# ADC.net
KiCad netlist of a schematic drawn in Altium Designer
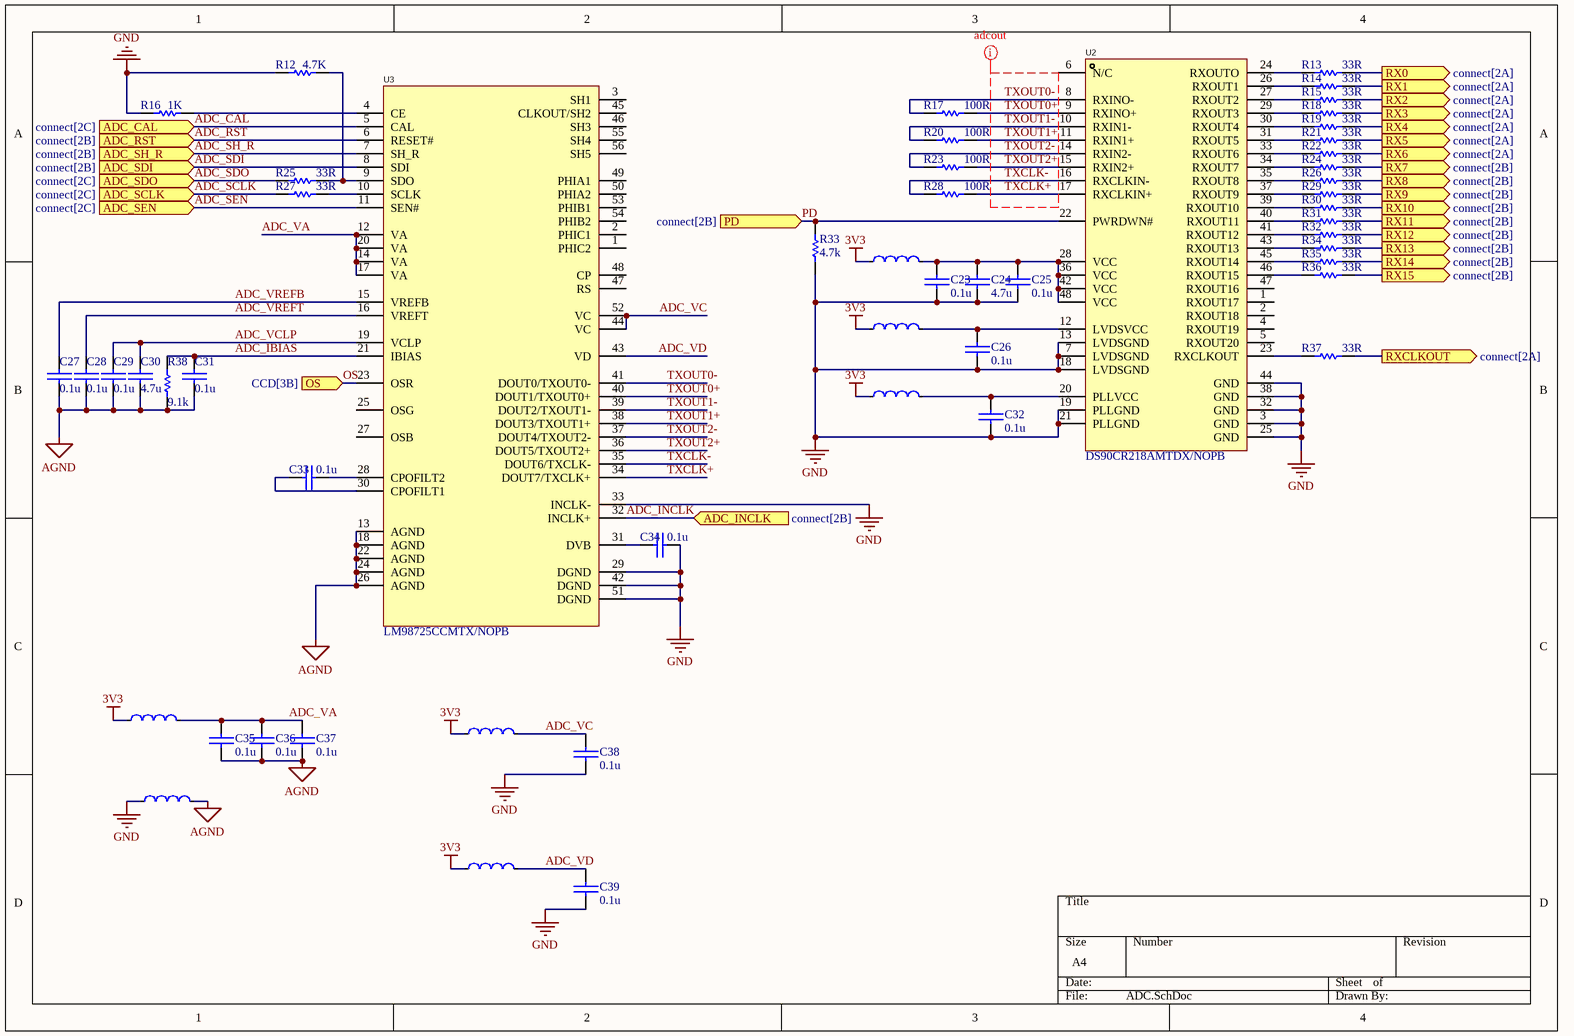
[diagram p0: ADC.SchDoc]

(export (version "E")
  (design (tool "Eeschema 10.0.6"))
  (components
    (comp (ref "C23")
      (value "0.1u")
      (footprint "0603C")
      (description "无极性电容")
      (libsource (lib "1.00-阻容感") (part "CAP"))
    )
    (comp (ref "C24")
      (value "4.7u")
      (footprint "0603C")
      (description "无极性电容")
      (libsource (lib "1.00-阻容感") (part "CAP"))
    )
    (comp (ref "C25")
      (value "0.1u")
      (footprint "0603C")
      (description "无极性电容")
      (libsource (lib "1.00-阻容感") (part "CAP"))
    )
    (comp (ref "C26")
      (value "0.1u")
      (footprint "0603C")
      (description "无极性电容")
      (libsource (lib "1.00-阻容感") (part "CAP"))
    )
    (comp (ref "C27")
      (value "0.1u")
      (footprint "0603C")
      (description "无极性电容")
      (libsource (lib "1.00-阻容感") (part "CAP"))
    )
    (comp (ref "C28")
      (value "0.1u")
      (footprint "0603C")
      (description "无极性电容")
      (libsource (lib "1.00-阻容感") (part "CAP"))
    )
    (comp (ref "C29")
      (value "0.1u")
      (footprint "0603C")
      (description "无极性电容")
      (libsource (lib "1.00-阻容感") (part "CAP"))
    )
    (comp (ref "C30")
      (value "4.7u")
      (footprint "0603C")
      (description "无极性电容")
      (libsource (lib "1.00-阻容感") (part "CAP"))
    )
    (comp (ref "C31")
      (value "0.1u")
      (footprint "0603C")
      (description "无极性电容")
      (libsource (lib "1.00-阻容感") (part "CAP"))
    )
    (comp (ref "C32")
      (value "0.1u")
      (footprint "0603C")
      (description "无极性电容")
      (libsource (lib "1.00-阻容感") (part "CAP"))
    )
    (comp (ref "C33")
      (value "0.1u")
      (footprint "0603C")
      (description "无极性电容")
      (libsource (lib "1.00-阻容感") (part "CAP"))
    )
    (comp (ref "C34")
      (value "0.1u")
      (footprint "0603C")
      (description "无极性电容")
      (libsource (lib "1.00-阻容感") (part "CAP"))
    )
    (comp (ref "C35")
      (value "0.1u")
      (footprint "0603C")
      (description "无极性电容")
      (libsource (lib "1.00-阻容感") (part "CAP"))
    )
    (comp (ref "C36")
      (value "0.1u")
      (footprint "0603C")
      (description "无极性电容")
      (libsource (lib "1.00-阻容感") (part "CAP"))
    )
    (comp (ref "C37")
      (value "0.1u")
      (footprint "0603C")
      (description "无极性电容")
      (libsource (lib "1.00-阻容感") (part "CAP"))
    )
    (comp (ref "C38")
      (value "0.1u")
      (footprint "0603C")
      (description "无极性电容")
      (libsource (lib "1.00-阻容感") (part "CAP"))
    )
    (comp (ref "C39")
      (value "0.1u")
      (footprint "0603C")
      (description "无极性电容")
      (libsource (lib "1.00-阻容感") (part "CAP"))
    )
    (comp (ref "L4")
      (value "GZ1608D601TF")
      (footprint "0603L")
      (description "铁氧体磁珠")
      (fields (field (name "MANUFACTURER") "Sunlord(顺络)") (field (name "TOLERANCE") "±25%"))
      (libsource (lib "1.00-阻容感") (part "FB"))
    )
    (comp (ref "L5")
      (value "GZ1608D601TF")
      (footprint "0603L")
      (description "铁氧体磁珠")
      (fields (field (name "MANUFACTURER") "Sunlord(顺络)") (field (name "TOLERANCE") "±25%"))
      (libsource (lib "1.00-阻容感") (part "FB"))
    )
    (comp (ref "L6")
      (value "GZ1608D601TF")
      (footprint "0603L")
      (description "铁氧体磁珠")
      (fields (field (name "MANUFACTURER") "Sunlord(顺络)") (field (name "TOLERANCE") "±25%"))
      (libsource (lib "1.00-阻容感") (part "FB"))
    )
    (comp (ref "L7")
      (value "GZ1608D601TF")
      (footprint "0603L")
      (description "铁氧体磁珠")
      (fields (field (name "MANUFACTURER") "Sunlord(顺络)") (field (name "TOLERANCE") "±25%"))
      (libsource (lib "1.00-阻容感") (part "FB"))
    )
    (comp (ref "L8")
      (value "GZ1608D601TF")
      (footprint "0603L")
      (description "铁氧体磁珠")
      (fields (field (name "MANUFACTURER") "Sunlord(顺络)") (field (name "TOLERANCE") "±25%"))
      (libsource (lib "1.00-阻容感") (part "FB"))
    )
    (comp (ref "L9")
      (value "GZ1608D601TF")
      (footprint "0603L")
      (description "铁氧体磁珠")
      (fields (field (name "MANUFACTURER") "Sunlord(顺络)") (field (name "TOLERANCE") "±25%"))
      (libsource (lib "1.00-阻容感") (part "FB"))
    )
    (comp (ref "L10")
      (value "GZ1608D601TF")
      (footprint "0603L")
      (description "铁氧体磁珠")
      (fields (field (name "MANUFACTURER") "Sunlord(顺络)") (field (name "TOLERANCE") "±25%"))
      (libsource (lib "1.00-阻容感") (part "FB"))
    )
    (comp (ref "R12")
      (value "4.7K")
      (footprint "0603R")
      (description "电阻")
      (libsource (lib "1.00-阻容感") (part "RES"))
    )
    (comp (ref "R13")
      (value "33R")
      (footprint "0603R")
      (description "电阻")
      (libsource (lib "1.00-阻容感") (part "RES"))
    )
    (comp (ref "R14")
      (value "33R")
      (footprint "0603R")
      (description "电阻")
      (libsource (lib "1.00-阻容感") (part "RES"))
    )
    (comp (ref "R15")
      (value "33R")
      (footprint "0603R")
      (description "电阻")
      (libsource (lib "1.00-阻容感") (part "RES"))
    )
    (comp (ref "R16")
      (value "1K")
      (footprint "0603R")
      (description "电阻")
      (libsource (lib "1.00-阻容感") (part "RES"))
    )
    (comp (ref "R17")
      (value "100R")
      (footprint "0603R")
      (description "电阻")
      (libsource (lib "1.00-阻容感") (part "RES"))
    )
    (comp (ref "R18")
      (value "33R")
      (footprint "0603R")
      (description "电阻")
      (libsource (lib "1.00-阻容感") (part "RES"))
    )
    (comp (ref "R19")
      (value "33R")
      (footprint "0603R")
      (description "电阻")
      (libsource (lib "1.00-阻容感") (part "RES"))
    )
    (comp (ref "R20")
      (value "100R")
      (footprint "0603R")
      (description "电阻")
      (libsource (lib "1.00-阻容感") (part "RES"))
    )
    (comp (ref "R21")
      (value "33R")
      (footprint "0603R")
      (description "电阻")
      (libsource (lib "1.00-阻容感") (part "RES"))
    )
    (comp (ref "R22")
      (value "33R")
      (footprint "0603R")
      (description "电阻")
      (libsource (lib "1.00-阻容感") (part "RES"))
    )
    (comp (ref "R23")
      (value "100R")
      (footprint "0603R")
      (description "电阻")
      (libsource (lib "1.00-阻容感") (part "RES"))
    )
    (comp (ref "R24")
      (value "33R")
      (footprint "0603R")
      (description "电阻")
      (libsource (lib "1.00-阻容感") (part "RES"))
    )
    (comp (ref "R25")
      (value "33R")
      (footprint "0603R")
      (description "电阻")
      (libsource (lib "1.00-阻容感") (part "RES"))
    )
    (comp (ref "R26")
      (value "33R")
      (footprint "0603R")
      (description "电阻")
      (libsource (lib "1.00-阻容感") (part "RES"))
    )
    (comp (ref "R27")
      (value "33R")
      (footprint "0603R")
      (description "电阻")
      (libsource (lib "1.00-阻容感") (part "RES"))
    )
    (comp (ref "R28")
      (value "100R")
      (footprint "0603R")
      (description "电阻")
      (libsource (lib "1.00-阻容感") (part "RES"))
    )
    (comp (ref "R29")
      (value "33R")
      (footprint "0603R")
      (description "电阻")
      (libsource (lib "1.00-阻容感") (part "RES"))
    )
    (comp (ref "R30")
      (value "33R")
      (footprint "0603R")
      (description "电阻")
      (libsource (lib "1.00-阻容感") (part "RES"))
    )
    (comp (ref "R31")
      (value "33R")
      (footprint "0603R")
      (description "电阻")
      (libsource (lib "1.00-阻容感") (part "RES"))
    )
    (comp (ref "R32")
      (value "33R")
      (footprint "0603R")
      (description "电阻")
      (libsource (lib "1.00-阻容感") (part "RES"))
    )
    (comp (ref "R33")
      (value "4.7k")
      (footprint "0603R")
      (description "电阻")
      (libsource (lib "1.00-阻容感") (part "RES"))
    )
    (comp (ref "R34")
      (value "33R")
      (footprint "0603R")
      (description "电阻")
      (libsource (lib "1.00-阻容感") (part "RES"))
    )
    (comp (ref "R35")
      (value "33R")
      (footprint "0603R")
      (description "电阻")
      (libsource (lib "1.00-阻容感") (part "RES"))
    )
    (comp (ref "R36")
      (value "33R")
      (footprint "0603R")
      (description "电阻")
      (libsource (lib "1.00-阻容感") (part "RES"))
    )
    (comp (ref "R37")
      (value "33R")
      (footprint "0603R")
      (description "电阻")
      (libsource (lib "1.00-阻容感") (part "RES"))
    )
    (comp (ref "R38")
      (value "9.1k")
      (footprint "0603R")
      (description "电阻")
      (libsource (lib "1.00-阻容感") (part "RES"))
    )
    (comp (ref "U2")
      (value "DS90CR218AMTDX/NOPB")
      (footprint "TSSOP-48")
      (description "解串芯片")
      (fields (field (name "MANUFACTURER") "TI(德州仪器)"))
      (libsource (lib "0.05-mylib") (part "DS90CR218AMTDX/NOPB"))
    )
    (comp (ref "U3")
      (value "LM98725CCMTX/NOPB")
      (footprint "TSSOP-56")
      (description "CCD专用ADC")
      (fields (field (name "MANUFACTURER") "TI(德州仪器)"))
      (libsource (lib "0.05-mylib") (part "LM98725CCMTX/NOPB"))
    )
  )
  (nets
    (net (code "1") (name "/ADC_CAL") (class "Default")
      (node (ref "U3") (pin "5") (pinfunction "CAL_5") (pintype "passive"))
    )
    (net (code "2") (name "/ADC_IBIAS") (class "Default")
      (node (ref "C31") (pin "1") (pinfunction "1_1") (pintype "passive"))
      (node (ref "R38") (pin "2") (pinfunction "2_2") (pintype "passive"))
      (node (ref "U3") (pin "21") (pinfunction "IBIAS_21") (pintype "passive"))
    )
    (net (code "3") (name "/ADC_INCLK") (class "Default")
      (node (ref "U3") (pin "32") (pinfunction "INCLK+_32") (pintype "passive"))
    )
    (net (code "4") (name "/ADC_RST") (class "Default")
      (node (ref "U3") (pin "6") (pinfunction "RESET#_6") (pintype "passive"))
    )
    (net (code "5") (name "/ADC_SCLK") (class "Default")
      (node (ref "R27") (pin "1") (pinfunction "1_1") (pintype "passive"))
    )
    (net (code "6") (name "/ADC_SDI") (class "Default")
      (node (ref "U3") (pin "8") (pinfunction "SDI_8") (pintype "passive"))
    )
    (net (code "7") (name "/ADC_SDO") (class "Default")
      (node (ref "R25") (pin "1") (pinfunction "1_1") (pintype "passive"))
    )
    (net (code "8") (name "/ADC_SEN") (class "Default")
      (node (ref "U3") (pin "11") (pinfunction "SEN#_11") (pintype "passive"))
    )
    (net (code "9") (name "/ADC_SH_R") (class "Default")
      (node (ref "U3") (pin "7") (pinfunction "SH_R_7") (pintype "passive"))
    )
    (net (code "10") (name "/ADC_VA") (class "Default")
      (node (ref "C35") (pin "2") (pinfunction "2_2") (pintype "passive"))
      (node (ref "C36") (pin "2") (pinfunction "2_2") (pintype "passive"))
      (node (ref "C37") (pin "2") (pinfunction "2_2") (pintype "passive"))
      (node (ref "L7") (pin "2") (pinfunction "2_2") (pintype "passive"))
      (node (ref "U3") (pin "12") (pinfunction "VA_12") (pintype "passive"))
      (node (ref "U3") (pin "14") (pinfunction "VA_14") (pintype "passive"))
      (node (ref "U3") (pin "17") (pinfunction "VA_17") (pintype "passive"))
      (node (ref "U3") (pin "20") (pinfunction "VA_20") (pintype "passive"))
    )
    (net (code "11") (name "/ADC_VC") (class "Default")
      (node (ref "C38") (pin "2") (pinfunction "2_2") (pintype "passive"))
      (node (ref "L8") (pin "2") (pinfunction "2_2") (pintype "passive"))
      (node (ref "U3") (pin "44") (pinfunction "VC_44") (pintype "passive"))
      (node (ref "U3") (pin "52") (pinfunction "VC_52") (pintype "passive"))
    )
    (net (code "12") (name "/ADC_VCLP") (class "Default")
      (node (ref "C29") (pin "1") (pinfunction "1_1") (pintype "passive"))
      (node (ref "C30") (pin "1") (pinfunction "1_1") (pintype "passive"))
      (node (ref "U3") (pin "19") (pinfunction "VCLP_19") (pintype "passive"))
    )
    (net (code "13") (name "/ADC_VD") (class "Default")
      (node (ref "C39") (pin "2") (pinfunction "2_2") (pintype "passive"))
      (node (ref "L10") (pin "2") (pinfunction "2_2") (pintype "passive"))
      (node (ref "U3") (pin "43") (pinfunction "VD_43") (pintype "passive"))
    )
    (net (code "14") (name "/ADC_VREFB") (class "Default")
      (node (ref "C27") (pin "1") (pinfunction "1_1") (pintype "passive"))
      (node (ref "U3") (pin "15") (pinfunction "VREFB_15") (pintype "passive"))
    )
    (net (code "15") (name "/ADC_VREFT") (class "Default")
      (node (ref "C28") (pin "1") (pinfunction "1_1") (pintype "passive"))
      (node (ref "U3") (pin "16") (pinfunction "VREFT_16") (pintype "passive"))
    )
    (net (code "16") (name "/OS") (class "Default")
      (node (ref "U3") (pin "23") (pinfunction "OSR_23") (pintype "passive"))
    )
    (net (code "17") (name "/PD") (class "Default")
      (node (ref "R33") (pin "2") (pinfunction "2_2") (pintype "passive"))
      (node (ref "U2") (pin "22") (pinfunction "PWRDWN#_22") (pintype "passive"))
    )
    (net (code "18") (name "/RX0") (class "Default")
      (node (ref "R13") (pin "2") (pinfunction "2_2") (pintype "passive"))
    )
    (net (code "19") (name "/RX1") (class "Default")
      (node (ref "R14") (pin "2") (pinfunction "2_2") (pintype "passive"))
    )
    (net (code "20") (name "/RX2") (class "Default")
      (node (ref "R15") (pin "2") (pinfunction "2_2") (pintype "passive"))
    )
    (net (code "21") (name "/RX3") (class "Default")
      (node (ref "R18") (pin "2") (pinfunction "2_2") (pintype "passive"))
    )
    (net (code "22") (name "/RX4") (class "Default")
      (node (ref "R19") (pin "2") (pinfunction "2_2") (pintype "passive"))
    )
    (net (code "23") (name "/RX5") (class "Default")
      (node (ref "R21") (pin "2") (pinfunction "2_2") (pintype "passive"))
    )
    (net (code "24") (name "/RX6") (class "Default")
      (node (ref "R22") (pin "2") (pinfunction "2_2") (pintype "passive"))
    )
    (net (code "25") (name "/RX7") (class "Default")
      (node (ref "R24") (pin "2") (pinfunction "2_2") (pintype "passive"))
    )
    (net (code "26") (name "/RX8") (class "Default")
      (node (ref "R26") (pin "2") (pinfunction "2_2") (pintype "passive"))
    )
    (net (code "27") (name "/RX9") (class "Default")
      (node (ref "R29") (pin "2") (pinfunction "2_2") (pintype "passive"))
    )
    (net (code "28") (name "/RX10") (class "Default")
      (node (ref "R30") (pin "2") (pinfunction "2_2") (pintype "passive"))
    )
    (net (code "29") (name "/RX11") (class "Default")
      (node (ref "R31") (pin "2") (pinfunction "2_2") (pintype "passive"))
    )
    (net (code "30") (name "/RX12") (class "Default")
      (node (ref "R32") (pin "2") (pinfunction "2_2") (pintype "passive"))
    )
    (net (code "31") (name "/RX13") (class "Default")
      (node (ref "R34") (pin "2") (pinfunction "2_2") (pintype "passive"))
    )
    (net (code "32") (name "/RX14") (class "Default")
      (node (ref "R35") (pin "2") (pinfunction "2_2") (pintype "passive"))
    )
    (net (code "33") (name "/RX15") (class "Default")
      (node (ref "R36") (pin "2") (pinfunction "2_2") (pintype "passive"))
    )
    (net (code "34") (name "/RXCLKOUT") (class "Default")
      (node (ref "R37") (pin "2") (pinfunction "2_2") (pintype "passive"))
    )
    (net (code "35") (name "/TXCLK+") (class "Default")
      (node (ref "R28") (pin "2") (pinfunction "2_2") (pintype "passive"))
      (node (ref "U2") (pin "17") (pinfunction "RXCLKIN+_17") (pintype "passive"))
      (node (ref "U3") (pin "34") (pinfunction "DOUT7/TXCLK+_34") (pintype "passive"))
    )
    (net (code "36") (name "/TXCLK-") (class "Default")
      (node (ref "R28") (pin "1") (pinfunction "1_1") (pintype "passive"))
      (node (ref "U2") (pin "16") (pinfunction "RXCLKIN-_16") (pintype "passive"))
      (node (ref "U3") (pin "35") (pinfunction "DOUT6/TXCLK-_35") (pintype "passive"))
    )
    (net (code "37") (name "/TXOUT0+") (class "Default")
      (node (ref "R17") (pin "2") (pinfunction "2_2") (pintype "passive"))
      (node (ref "U2") (pin "9") (pinfunction "RXINO+_9") (pintype "passive"))
      (node (ref "U3") (pin "40") (pinfunction "DOUT1/TXOUT0+_40") (pintype "passive"))
    )
    (net (code "38") (name "/TXOUT0-") (class "Default")
      (node (ref "R17") (pin "1") (pinfunction "1_1") (pintype "passive"))
      (node (ref "U2") (pin "8") (pinfunction "RXINO-_8") (pintype "passive"))
      (node (ref "U3") (pin "41") (pinfunction "DOUT0/TXOUT0-_41") (pintype "passive"))
    )
    (net (code "39") (name "/TXOUT1+") (class "Default")
      (node (ref "R20") (pin "2") (pinfunction "2_2") (pintype "passive"))
      (node (ref "U2") (pin "11") (pinfunction "RXIN1+_11") (pintype "passive"))
      (node (ref "U3") (pin "38") (pinfunction "DOUT3/TXOUT1+_38") (pintype "passive"))
    )
    (net (code "40") (name "/TXOUT1-") (class "Default")
      (node (ref "R20") (pin "1") (pinfunction "1_1") (pintype "passive"))
      (node (ref "U2") (pin "10") (pinfunction "RXIN1-_10") (pintype "passive"))
      (node (ref "U3") (pin "39") (pinfunction "DOUT2/TXOUT1-_39") (pintype "passive"))
    )
    (net (code "41") (name "/TXOUT2+") (class "Default")
      (node (ref "R23") (pin "2") (pinfunction "2_2") (pintype "passive"))
      (node (ref "U2") (pin "15") (pinfunction "RXIN2+_15") (pintype "passive"))
      (node (ref "U3") (pin "36") (pinfunction "DOUT5/TXOUT2+_36") (pintype "passive"))
    )
    (net (code "42") (name "/TXOUT2-") (class "Default")
      (node (ref "R23") (pin "1") (pinfunction "1_1") (pintype "passive"))
      (node (ref "U2") (pin "14") (pinfunction "RXIN2-_14") (pintype "passive"))
      (node (ref "U3") (pin "37") (pinfunction "DOUT4/TXOUT2-_37") (pintype "passive"))
    )
    (net (code "43") (name "3V3") (class "Default")
      (node (ref "L10") (pin "1") (pinfunction "1_1") (pintype "passive"))
      (node (ref "L4") (pin "1") (pinfunction "1_1") (pintype "passive"))
      (node (ref "L5") (pin "1") (pinfunction "1_1") (pintype "passive"))
      (node (ref "L6") (pin "1") (pinfunction "1_1") (pintype "passive"))
      (node (ref "L7") (pin "1") (pinfunction "1_1") (pintype "passive"))
      (node (ref "L8") (pin "1") (pinfunction "1_1") (pintype "passive"))
    )
    (net (code "44") (name "AGND") (class "Default")
      (node (ref "C27") (pin "2") (pinfunction "2_2") (pintype "passive"))
      (node (ref "C28") (pin "2") (pinfunction "2_2") (pintype "passive"))
      (node (ref "C29") (pin "2") (pinfunction "2_2") (pintype "passive"))
      (node (ref "C30") (pin "2") (pinfunction "2_2") (pintype "passive"))
      (node (ref "C31") (pin "2") (pinfunction "2_2") (pintype "passive"))
      (node (ref "C35") (pin "1") (pinfunction "1_1") (pintype "passive"))
      (node (ref "C36") (pin "1") (pinfunction "1_1") (pintype "passive"))
      (node (ref "C37") (pin "1") (pinfunction "1_1") (pintype "passive"))
      (node (ref "L9") (pin "2") (pinfunction "2_2") (pintype "passive"))
      (node (ref "R38") (pin "1") (pinfunction "1_1") (pintype "passive"))
      (node (ref "U3") (pin "13") (pinfunction "AGND_13") (pintype "passive"))
      (node (ref "U3") (pin "18") (pinfunction "AGND_18") (pintype "passive"))
      (node (ref "U3") (pin "22") (pinfunction "AGND_22") (pintype "passive"))
      (node (ref "U3") (pin "24") (pinfunction "AGND_24") (pintype "passive"))
      (node (ref "U3") (pin "26") (pinfunction "AGND_26") (pintype "passive"))
    )
    (net (code "45") (name "GND") (class "Default")
      (node (ref "C23") (pin "1") (pinfunction "1_1") (pintype "passive"))
      (node (ref "C24") (pin "1") (pinfunction "1_1") (pintype "passive"))
      (node (ref "C25") (pin "1") (pinfunction "1_1") (pintype "passive"))
      (node (ref "C26") (pin "1") (pinfunction "1_1") (pintype "passive"))
      (node (ref "C32") (pin "1") (pinfunction "1_1") (pintype "passive"))
      (node (ref "C34") (pin "2") (pinfunction "2_2") (pintype "passive"))
      (node (ref "C38") (pin "1") (pinfunction "1_1") (pintype "passive"))
      (node (ref "C39") (pin "1") (pinfunction "1_1") (pintype "passive"))
      (node (ref "L9") (pin "1") (pinfunction "1_1") (pintype "passive"))
      (node (ref "R12") (pin "1") (pinfunction "1_1") (pintype "passive"))
      (node (ref "R16") (pin "1") (pinfunction "1_1") (pintype "passive"))
      (node (ref "R33") (pin "1") (pinfunction "1_1") (pintype "passive"))
      (node (ref "U2") (pin "13") (pinfunction "LVDSGND_13") (pintype "passive"))
      (node (ref "U2") (pin "18") (pinfunction "LVDSGND_18") (pintype "passive"))
      (node (ref "U2") (pin "19") (pinfunction "PLLGND_19") (pintype "passive"))
      (node (ref "U2") (pin "21") (pinfunction "PLLGND_21") (pintype "passive"))
      (node (ref "U2") (pin "25") (pinfunction "GND_25") (pintype "passive"))
      (node (ref "U2") (pin "3") (pinfunction "GND_3") (pintype "passive"))
      (node (ref "U2") (pin "32") (pinfunction "GND_32") (pintype "passive"))
      (node (ref "U2") (pin "38") (pinfunction "GND_38") (pintype "passive"))
      (node (ref "U2") (pin "44") (pinfunction "GND_44") (pintype "passive"))
      (node (ref "U2") (pin "7") (pinfunction "LVDSGND_7") (pintype "passive"))
      (node (ref "U3") (pin "29") (pinfunction "DGND_29") (pintype "passive"))
      (node (ref "U3") (pin "33") (pinfunction "INCLK-_33") (pintype "passive"))
      (node (ref "U3") (pin "42") (pinfunction "DGND_42") (pintype "passive"))
      (node (ref "U3") (pin "51") (pinfunction "DGND_51") (pintype "passive"))
    )
    (net (code "46") (name "Net-(C23-Pad2)") (class "Default")
      (node (ref "C23") (pin "2") (pinfunction "2_2") (pintype "passive"))
      (node (ref "C24") (pin "2") (pinfunction "2_2") (pintype "passive"))
      (node (ref "C25") (pin "2") (pinfunction "2_2") (pintype "passive"))
      (node (ref "L4") (pin "2") (pinfunction "2_2") (pintype "passive"))
      (node (ref "U2") (pin "28") (pinfunction "VCC_28") (pintype "passive"))
      (node (ref "U2") (pin "36") (pinfunction "VCC_36") (pintype "passive"))
      (node (ref "U2") (pin "42") (pinfunction "VCC_42") (pintype "passive"))
      (node (ref "U2") (pin "48") (pinfunction "VCC_48") (pintype "passive"))
    )
    (net (code "47") (name "Net-(U2-LVDSVCC)") (class "Default")
      (node (ref "C26") (pin "2") (pinfunction "2_2") (pintype "passive"))
      (node (ref "L5") (pin "2") (pinfunction "2_2") (pintype "passive"))
      (node (ref "U2") (pin "12") (pinfunction "LVDSVCC_12") (pintype "passive"))
    )
    (net (code "48") (name "Net-(U2-PLLVCC)") (class "Default")
      (node (ref "C32") (pin "2") (pinfunction "2_2") (pintype "passive"))
      (node (ref "L6") (pin "2") (pinfunction "2_2") (pintype "passive"))
      (node (ref "U2") (pin "20") (pinfunction "PLLVCC_20") (pintype "passive"))
    )
    (net (code "49") (name "Net-(U2-RXCLKOUT)") (class "Default")
      (node (ref "R37") (pin "1") (pinfunction "1_1") (pintype "passive"))
      (node (ref "U2") (pin "23") (pinfunction "RXCLKOUT_23") (pintype "passive"))
    )
    (net (code "50") (name "Net-(U2-RXOUT1)") (class "Default")
      (node (ref "R14") (pin "1") (pinfunction "1_1") (pintype "passive"))
      (node (ref "U2") (pin "26") (pinfunction "RXOUT1_26") (pintype "passive"))
    )
    (net (code "51") (name "Net-(U2-RXOUT2)") (class "Default")
      (node (ref "R15") (pin "1") (pinfunction "1_1") (pintype "passive"))
      (node (ref "U2") (pin "27") (pinfunction "RXOUT2_27") (pintype "passive"))
    )
    (net (code "52") (name "Net-(U2-RXOUT3)") (class "Default")
      (node (ref "R18") (pin "1") (pinfunction "1_1") (pintype "passive"))
      (node (ref "U2") (pin "29") (pinfunction "RXOUT3_29") (pintype "passive"))
    )
    (net (code "53") (name "Net-(U2-RXOUT4)") (class "Default")
      (node (ref "R19") (pin "1") (pinfunction "1_1") (pintype "passive"))
      (node (ref "U2") (pin "30") (pinfunction "RXOUT4_30") (pintype "passive"))
    )
    (net (code "54") (name "Net-(U2-RXOUT5)") (class "Default")
      (node (ref "R21") (pin "1") (pinfunction "1_1") (pintype "passive"))
      (node (ref "U2") (pin "31") (pinfunction "RXOUT5_31") (pintype "passive"))
    )
    (net (code "55") (name "Net-(U2-RXOUT6)") (class "Default")
      (node (ref "R22") (pin "1") (pinfunction "1_1") (pintype "passive"))
      (node (ref "U2") (pin "33") (pinfunction "RXOUT6_33") (pintype "passive"))
    )
    (net (code "56") (name "Net-(U2-RXOUT7)") (class "Default")
      (node (ref "R24") (pin "1") (pinfunction "1_1") (pintype "passive"))
      (node (ref "U2") (pin "34") (pinfunction "RXOUT7_34") (pintype "passive"))
    )
    (net (code "57") (name "Net-(U2-RXOUT8)") (class "Default")
      (node (ref "R26") (pin "1") (pinfunction "1_1") (pintype "passive"))
      (node (ref "U2") (pin "35") (pinfunction "RXOUT8_35") (pintype "passive"))
    )
    (net (code "58") (name "Net-(U2-RXOUT9)") (class "Default")
      (node (ref "R29") (pin "1") (pinfunction "1_1") (pintype "passive"))
      (node (ref "U2") (pin "37") (pinfunction "RXOUT9_37") (pintype "passive"))
    )
    (net (code "59") (name "Net-(U2-RXOUT10)") (class "Default")
      (node (ref "R30") (pin "1") (pinfunction "1_1") (pintype "passive"))
      (node (ref "U2") (pin "39") (pinfunction "RXOUT10_39") (pintype "passive"))
    )
    (net (code "60") (name "Net-(U2-RXOUT11)") (class "Default")
      (node (ref "R31") (pin "1") (pinfunction "1_1") (pintype "passive"))
      (node (ref "U2") (pin "40") (pinfunction "RXOUT11_40") (pintype "passive"))
    )
    (net (code "61") (name "Net-(U2-RXOUT12)") (class "Default")
      (node (ref "R32") (pin "1") (pinfunction "1_1") (pintype "passive"))
      (node (ref "U2") (pin "41") (pinfunction "RXOUT12_41") (pintype "passive"))
    )
    (net (code "62") (name "Net-(U2-RXOUT13)") (class "Default")
      (node (ref "R34") (pin "1") (pinfunction "1_1") (pintype "passive"))
      (node (ref "U2") (pin "43") (pinfunction "RXOUT13_43") (pintype "passive"))
    )
    (net (code "63") (name "Net-(U2-RXOUT14)") (class "Default")
      (node (ref "R35") (pin "1") (pinfunction "1_1") (pintype "passive"))
      (node (ref "U2") (pin "45") (pinfunction "RXOUT14_45") (pintype "passive"))
    )
    (net (code "64") (name "Net-(U2-RXOUT15)") (class "Default")
      (node (ref "R36") (pin "1") (pinfunction "1_1") (pintype "passive"))
      (node (ref "U2") (pin "46") (pinfunction "RXOUT15_46") (pintype "passive"))
    )
    (net (code "65") (name "Net-(U2-RXOUTO)") (class "Default")
      (node (ref "R13") (pin "1") (pinfunction "1_1") (pintype "passive"))
      (node (ref "U2") (pin "24") (pinfunction "RXOUTO_24") (pintype "passive"))
    )
    (net (code "66") (name "Net-(U3-CE)") (class "Default")
      (node (ref "R16") (pin "2") (pinfunction "2_2") (pintype "passive"))
      (node (ref "U3") (pin "4") (pinfunction "CE_4") (pintype "passive"))
    )
    (net (code "67") (name "Net-(U3-CPOFILT1)") (class "Default")
      (node (ref "C33") (pin "1") (pinfunction "1_1") (pintype "passive"))
      (node (ref "U3") (pin "30") (pinfunction "CPOFILT1_30") (pintype "passive"))
    )
    (net (code "68") (name "Net-(U3-CPOFILT2)") (class "Default")
      (node (ref "C33") (pin "2") (pinfunction "2_2") (pintype "passive"))
      (node (ref "U3") (pin "28") (pinfunction "CPOFILT2_28") (pintype "passive"))
    )
    (net (code "69") (name "Net-(U3-DVB)") (class "Default")
      (node (ref "C34") (pin "1") (pinfunction "1_1") (pintype "passive"))
      (node (ref "U3") (pin "31") (pinfunction "DVB_31") (pintype "passive"))
    )
    (net (code "70") (name "Net-(U3-SCLK)") (class "Default")
      (node (ref "R27") (pin "2") (pinfunction "2_2") (pintype "passive"))
      (node (ref "U3") (pin "10") (pinfunction "SCLK_10") (pintype "passive"))
    )
    (net (code "71") (name "Net-(U3-SDO)") (class "Default")
      (node (ref "R12") (pin "2") (pinfunction "2_2") (pintype "passive"))
      (node (ref "R25") (pin "2") (pinfunction "2_2") (pintype "passive"))
      (node (ref "U3") (pin "9") (pinfunction "SDO_9") (pintype "passive"))
    )
    (net (code "72") (name "unconnected-(U2-N{slash}C-Pad6)") (class "Default")
      (node (ref "U2") (pin "6") (pinfunction "N/C_6") (pintype "passive"))
    )
    (net (code "73") (name "unconnected-(U2-RXOUT16-Pad47)") (class "Default")
      (node (ref "U2") (pin "47") (pinfunction "RXOUT16_47") (pintype "passive"))
    )
    (net (code "74") (name "unconnected-(U2-RXOUT17-Pad1)") (class "Default")
      (node (ref "U2") (pin "1") (pinfunction "RXOUT17_1") (pintype "passive"))
    )
    (net (code "75") (name "unconnected-(U2-RXOUT18-Pad2)") (class "Default")
      (node (ref "U2") (pin "2") (pinfunction "RXOUT18_2") (pintype "passive"))
    )
    (net (code "76") (name "unconnected-(U2-RXOUT19-Pad4)") (class "Default")
      (node (ref "U2") (pin "4") (pinfunction "RXOUT19_4") (pintype "passive"))
    )
    (net (code "77") (name "unconnected-(U2-RXOUT20-Pad5)") (class "Default")
      (node (ref "U2") (pin "5") (pinfunction "RXOUT20_5") (pintype "passive"))
    )
    (net (code "78") (name "unconnected-(U3-CLKOUT{slash}SH2-Pad45)") (class "Default")
      (node (ref "U3") (pin "45") (pinfunction "CLKOUT/SH2_45") (pintype "passive"))
    )
    (net (code "79") (name "unconnected-(U3-CP-Pad48)") (class "Default")
      (node (ref "U3") (pin "48") (pinfunction "CP_48") (pintype "passive"))
    )
    (net (code "80") (name "unconnected-(U3-OSB-Pad27)") (class "Default")
      (node (ref "U3") (pin "27") (pinfunction "OSB_27") (pintype "passive"))
    )
    (net (code "81") (name "unconnected-(U3-OSG-Pad25)") (class "Default")
      (node (ref "U3") (pin "25") (pinfunction "OSG_25") (pintype "passive"))
    )
    (net (code "82") (name "unconnected-(U3-PHIA1-Pad49)") (class "Default")
      (node (ref "U3") (pin "49") (pinfunction "PHIA1_49") (pintype "passive"))
    )
    (net (code "83") (name "unconnected-(U3-PHIA2-Pad50)") (class "Default")
      (node (ref "U3") (pin "50") (pinfunction "PHIA2_50") (pintype "passive"))
    )
    (net (code "84") (name "unconnected-(U3-PHIB1-Pad53)") (class "Default")
      (node (ref "U3") (pin "53") (pinfunction "PHIB1_53") (pintype "passive"))
    )
    (net (code "85") (name "unconnected-(U3-PHIB2-Pad54)") (class "Default")
      (node (ref "U3") (pin "54") (pinfunction "PHIB2_54") (pintype "passive"))
    )
    (net (code "86") (name "unconnected-(U3-PHIC1-Pad2)") (class "Default")
      (node (ref "U3") (pin "2") (pinfunction "PHIC1_2") (pintype "passive"))
    )
    (net (code "87") (name "unconnected-(U3-PHIC2-Pad1)") (class "Default")
      (node (ref "U3") (pin "1") (pinfunction "PHIC2_1") (pintype "passive"))
    )
    (net (code "88") (name "unconnected-(U3-RS-Pad47)") (class "Default")
      (node (ref "U3") (pin "47") (pinfunction "RS_47") (pintype "passive"))
    )
    (net (code "89") (name "unconnected-(U3-SH1-Pad3)") (class "Default")
      (node (ref "U3") (pin "3") (pinfunction "SH1_3") (pintype "passive"))
    )
    (net (code "90") (name "unconnected-(U3-SH3-Pad46)") (class "Default")
      (node (ref "U3") (pin "46") (pinfunction "SH3_46") (pintype "passive"))
    )
    (net (code "91") (name "unconnected-(U3-SH4-Pad55)") (class "Default")
      (node (ref "U3") (pin "55") (pinfunction "SH4_55") (pintype "passive"))
    )
    (net (code "92") (name "unconnected-(U3-SH5-Pad56)") (class "Default")
      (node (ref "U3") (pin "56") (pinfunction "SH5_56") (pintype "passive"))
    )
  )
)
